# Power.net
KiCad netlist of a schematic drawn in Altium Designer
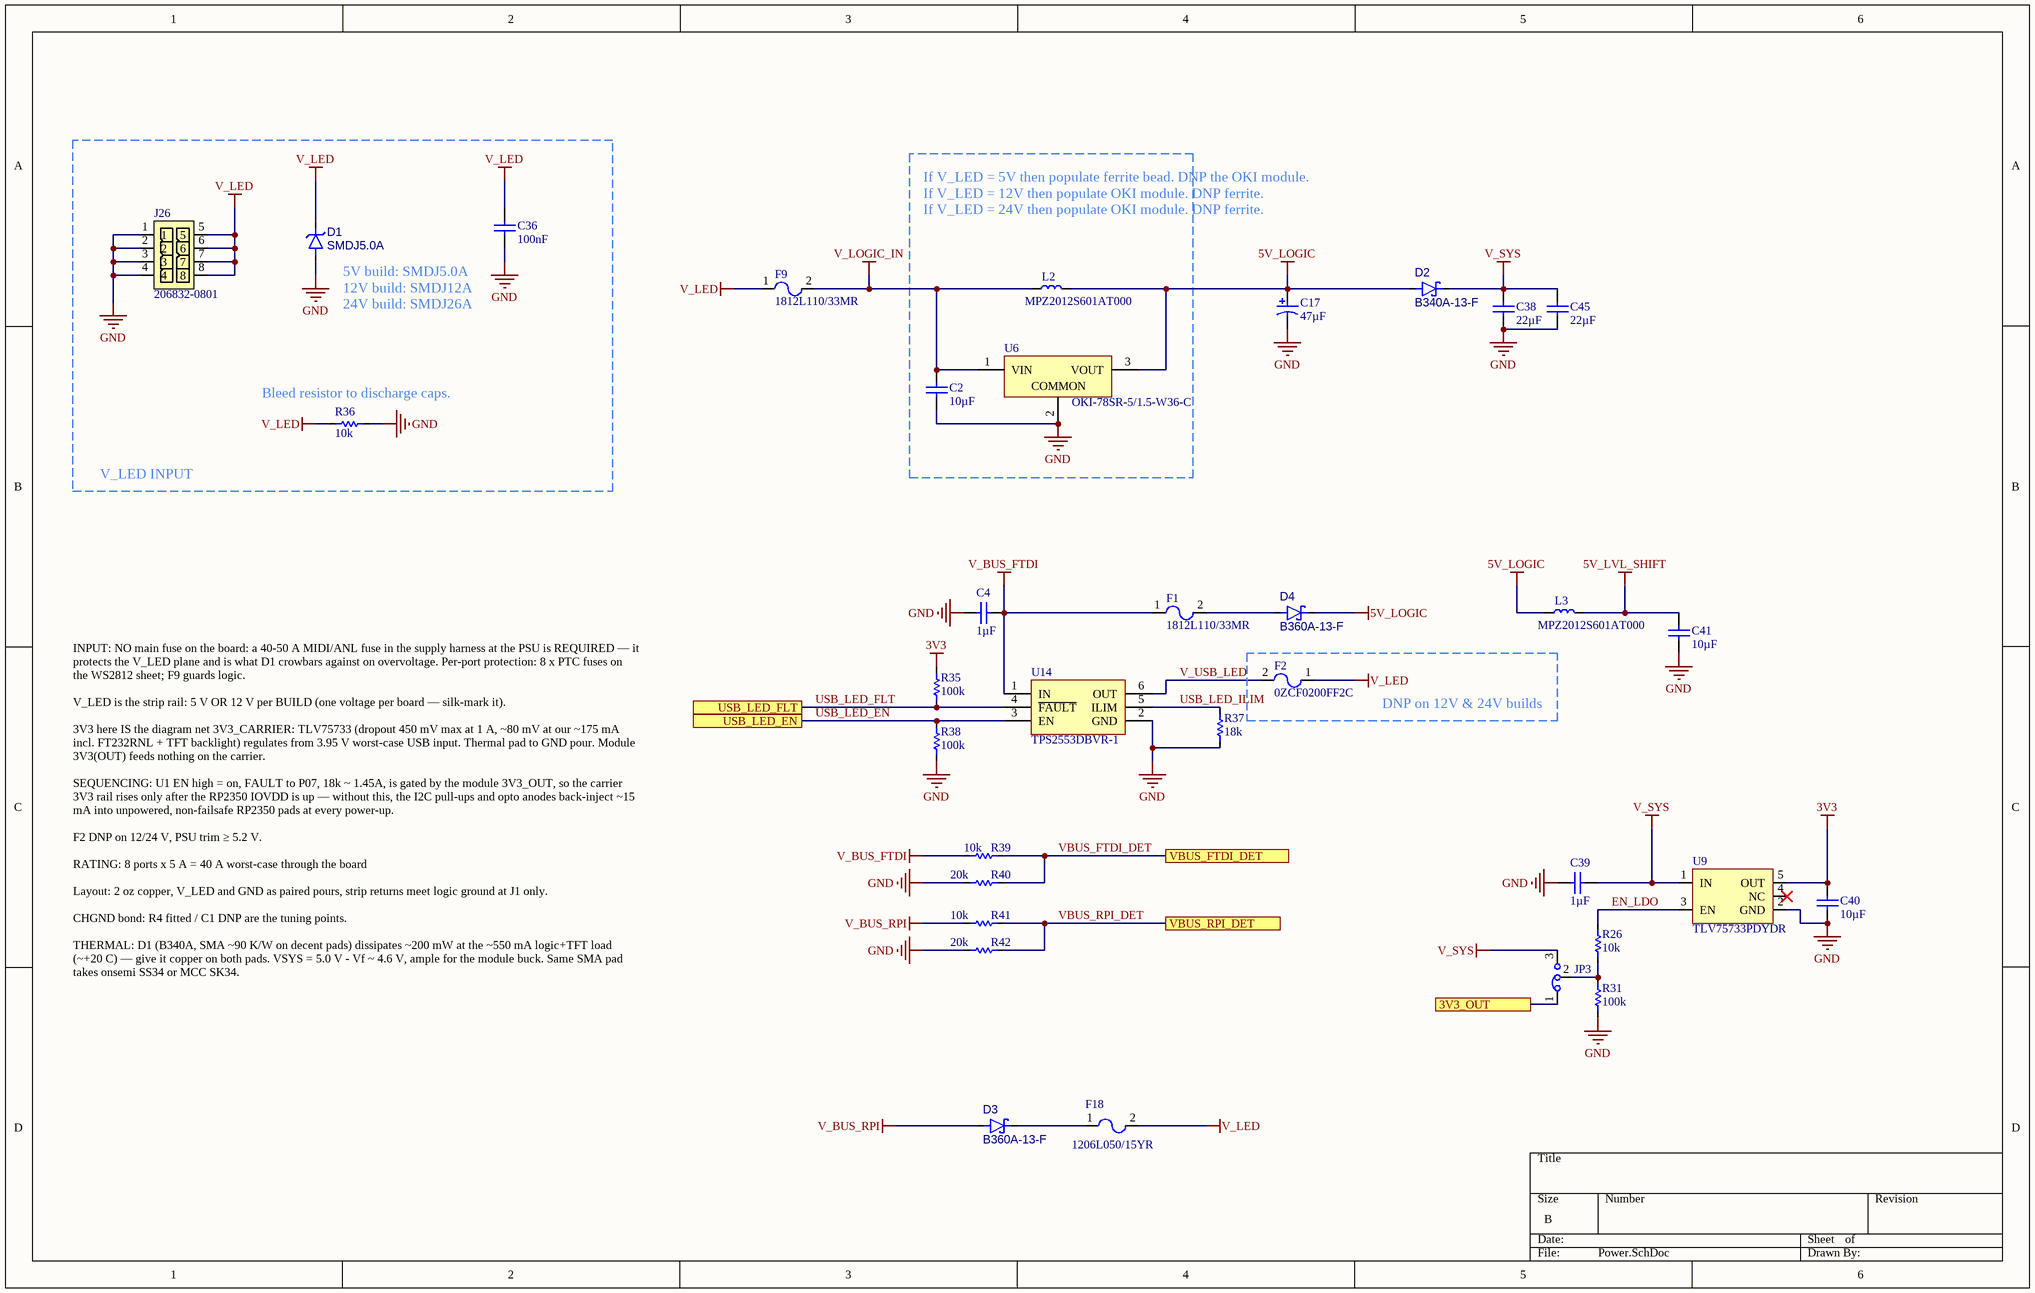
[diagram p0: Power.SchDoc]

(export (version "E")
  (design (tool "Eeschema 10.0.6"))
  (components
    (comp (ref "C2")
      (value "10µF")
      (footprint "CAPC2012X14N_0805_MED")
      (description "Ceramic Capacitor, Multilayer, Ceramic, 10uF, 50V, 10%, X6S, 0805")
      (fields (field (name "TOLERANCE") "10%") (field (name "Comment") "GRM21BR61H106KE43L"))
      (libsource (lib "Equus Computer Systems") (part "CAP-NP-2"))
    )
    (comp (ref "C4")
      (value "1µF")
      (footprint "CAPC1608X10N_0603_MED")
      (fields (field (name "TOLERANCE") "10%") (field (name "Comment") "C1608X7R1C105K080AC"))
      (libsource (lib "Equus Computer Systems") (part "CAP-NP-2"))
    )
    (comp (ref "C17")
      (value "47µF")
      (footprint "FP-SP-Cap-X-MFG")
      (description "Polymer Aluminum Electrolytic Capacitor, 47 µF, -55 to 105 ¡C")
      (fields (field (name "TOLERANCE") "20%") (field (name "Comment") "EEF-CX1C470R"))
      (libsource (lib "Equus Computer Systems") (part "CAP-P-2"))
    )
    (comp (ref "C36")
      (value "100nF")
      (footprint "CAPC1608X10N_0603_MED")
      (fields (field (name "Comment") "CC0603KRX7R0BB104"))
      (libsource (lib "Equus Computer Systems") (part "CAP-NP-2"))
    )
    (comp (ref "C38")
      (value "22µF")
      (footprint "CAPC2012X14N_0805_MED")
      (description "Ceramic Capacitor, Multilayer, Ceramic, 22uF, 16V, 20%, X6S, 0805")
      (fields (field (name "TOLERANCE") "20%") (field (name "Comment") "GRM21BC81C226ME44L"))
      (libsource (lib "Equus Computer Systems") (part "CAP-NP-2"))
    )
    (comp (ref "C39")
      (value "1µF")
      (footprint "CAPC1608X10N_0603_MED")
      (fields (field (name "TOLERANCE") "10%") (field (name "Comment") "C1608X7R1C105K080AC"))
      (libsource (lib "Equus Computer Systems") (part "CAP-NP-2"))
    )
    (comp (ref "C40")
      (value "10µF")
      (footprint "CAPC2012X14N_0805_MED")
      (description "Ceramic Capacitor, Multilayer, Ceramic, 10uF, 16V, 10%, X6S, 0805")
      (fields (field (name "TOLERANCE") "10%") (field (name "Comment") "GRM21BC81C106KA73L"))
      (libsource (lib "Equus Computer Systems") (part "CAP-NP-2"))
    )
    (comp (ref "C41")
      (value "10µF")
      (footprint "CAPC2012X14N_0805_MED")
      (description "Ceramic Capacitor, Multilayer, Ceramic, 10uF, 16V, 10%, X6S, 0805")
      (fields (field (name "TOLERANCE") "10%") (field (name "Comment") "GRM21BC81C106KA73L"))
      (libsource (lib "Equus Computer Systems") (part "CAP-NP-2"))
    )
    (comp (ref "C45")
      (value "22µF")
      (footprint "CAPC2012X14N_0805_MED")
      (description "Ceramic Capacitor, Multilayer, Ceramic, 22uF, 16V, 20%, X6S, 0805")
      (fields (field (name "TOLERANCE") "20%") (field (name "Comment") "GRM21BC81C226ME44L"))
      (libsource (lib "Equus Computer Systems") (part "CAP-NP-2"))
    )
    (comp (ref "D1")
      (value "SMDJ5.0A")
      (footprint "SMDJ_DO-214AB")
      (description "SMDJ Series 6.5 W 7 V Uni-Directional Surface Mount TVS Diode - SMC")
      (libsource (lib "Equus Computer Systems") (part "DIODE-TVS-2"))
    )
    (comp (ref "D2")
      (value "B340A-13-F")
      (footprint "DO-214AC_SMA")
      (description "Rectifier Diode, Schottky, 1 Phase, 1 Element, 3A, 40V V(RRM), Silicon")
      (libsource (lib "Equus Computer Systems") (part "DIODE-SKY-2"))
    )
    (comp (ref "D3")
      (value "B360A-13-F")
      (footprint "FP-SMA-MFG")
      (description "Rectifier Diode, Schottky, 1 Phase, 1 Element, 3A, 60V V(RRM), Silicon, DO-214AC")
      (libsource (lib "Equus Computer Systems") (part "DIODE-SKY-2"))
    )
    (comp (ref "D4")
      (value "B360A-13-F")
      (footprint "FP-SMA-MFG")
      (description "Rectifier Diode, Schottky, 1 Phase, 1 Element, 3A, 60V V(RRM), Silicon, DO-214AC")
      (libsource (lib "Equus Computer Systems") (part "DIODE-SKY-2"))
    )
    (comp (ref "F1")
      (value "1812L110/33MR")
      (footprint "FUSE4532X1.55N_1812MED")
      (description "PTC Resettable Fuse 1.1A(hold) 1.95A(trip) 33VDC 20A 0.8W 0.5s 0.06Ohm SMD Solder Pad 1812 T/R")
      (libsource (lib "Equus Computer Systems") (part "Fuse"))
    )
    (comp (ref "F2")
      (value "0ZCF0200FF2C")
      (footprint "RESC7451X90M_2920")
      (description "SMD Resettable Fuse, PPTC, 2920 [7351 Metric], 0ZCF, 16 VDC, 2 A, 4 A, 4.5 s")
      (libsource (lib "Equus Computer Systems") (part "Fuse"))
    )
    (comp (ref "F9")
      (value "1812L110/33MR")
      (footprint "FUSE4532X1.55N_1812MED")
      (description "PTC Resettable Fuse 1.1A(hold) 1.95A(trip) 33VDC 20A 0.8W 0.5s 0.06Ohm SMD Solder Pad 1812 T/R")
      (libsource (lib "Equus Computer Systems") (part "Fuse"))
    )
    (comp (ref "F18")
      (value "1206L050/15YR")
      (footprint "FP-1206L-MFG")
      (description "PTC Resettable Fuse 0.5A(hold) 1A(trip) 15VDC 100A 0.6W 0.1s 0.15Ohm SMD Solder Pad 1206 T/R")
      (libsource (lib "Equus Computer Systems") (part "Fuse"))
    )
    (comp (ref "J26")
      (value "206832-0801")
      (footprint "206832-0801-Footprint-1")
      (description "Micro-Fit+, Vertical Header, 8 pin")
      (libsource (lib "Equus Computer Systems") (part "206832-0801-Symbol-1"))
    )
    (comp (ref "JP3")
      (value "Jumper 3 x 1 Bridge 1-2 Solder Bridge")
      (footprint "Jumper 3 Solder Bridge 1-2 0603")
      (description "0603 Solder Bridge Jumper Surface Mount")
      (fields (field (name "TOLERANCE") "1%"))
      (libsource (lib "Equus Computer Systems") (part "Jumper 3 Bridge 12"))
    )
    (comp (ref "L2")
      (value "MPZ2012S601AT000")
      (footprint "FP-MPZ2012-MFG")
      (description "Ferrite Beads Multi-Layer Power 600Ohm 25% 100MHz 2A 0.1Ohm DCR 0805 T/R")
      (fields (field (name "TOLERANCE") "25%"))
      (libsource (lib "Equus Computer Systems") (part "IND-2"))
    )
    (comp (ref "L3")
      (value "MPZ2012S601AT000")
      (footprint "FP-MPZ2012-MFG")
      (description "Ferrite Beads Multi-Layer Power 600Ohm 25% 100MHz 2A 0.1Ohm DCR 0805 T/R")
      (fields (field (name "TOLERANCE") "25%"))
      (libsource (lib "Equus Computer Systems") (part "IND-2"))
    )
    (comp (ref "R26")
      (value "10k")
      (footprint "RESC1608X06N_0603_MED")
      (fields
        (field (name "POWER") "100mW")
        (field (name "TOLERANCE") "1%")
        (field (name "Comment") "RC0603FR-1010KL")
      )
      (libsource (lib "Equus Computer Systems") (part "RES-2"))
    )
    (comp (ref "R31")
      (value "100k")
      (footprint "RESC1608X06N_0603_MED")
      (fields
        (field (name "POWER") "100mW")
        (field (name "TOLERANCE") "0.5%")
        (field (name "Comment") "RC0603DR-07100KL")
      )
      (libsource (lib "Equus Computer Systems") (part "RES-2"))
    )
    (comp (ref "R35")
      (value "100k")
      (footprint "RESC1608X06N_0603_MED")
      (fields
        (field (name "POWER") "100mW")
        (field (name "TOLERANCE") "0.5%")
        (field (name "Comment") "RC0603DR-07100KL")
      )
      (libsource (lib "Equus Computer Systems") (part "RES-2"))
    )
    (comp (ref "R36")
      (value "10k")
      (footprint "RESC3116X06N_1206MED")
      (fields
        (field (name "POWER") "250mW")
        (field (name "TOLERANCE") "1%")
        (field (name "Comment") "RC1206FR-0710KL")
      )
      (libsource (lib "Equus Computer Systems") (part "RES-2"))
    )
    (comp (ref "R37")
      (value "18k")
      (footprint "RESC1608X06N_0603_MED")
      (description "100mW Thick Film Resistors 75V ±100ppm/℃ ±1% 18kΩ 0603 Chip Resistor - Surface Mount ROHS")
      (fields (field (name "TOLERANCE") "1%") (field (name "POWER") "100mW"))
      (libsource (lib "Equus Computer Systems") (part "RES-2"))
    )
    (comp (ref "R38")
      (value "100k")
      (footprint "RESC1608X06N_0603_MED")
      (fields
        (field (name "POWER") "100mW")
        (field (name "TOLERANCE") "0.5%")
        (field (name "Comment") "RC0603DR-07100KL")
      )
      (libsource (lib "Equus Computer Systems") (part "RES-2"))
    )
    (comp (ref "R39")
      (value "10k")
      (footprint "RESC1608X06N_0603_MED")
      (fields
        (field (name "POWER") "100mW")
        (field (name "TOLERANCE") "1%")
        (field (name "Comment") "RC0603FR-1010KL")
      )
      (libsource (lib "Equus Computer Systems") (part "RES-2"))
    )
    (comp (ref "R40")
      (value "20k")
      (footprint "RESC1608X06N_0603_MED")
      (description "100mW Thick Film Resistors 75V ±100ppm/℃ ±1% 20kΩ 0603 Chip Resistor - Surface Mount ROHS")
      (fields (field (name "TOLERANCE") "1%") (field (name "POWER") "100mW"))
      (libsource (lib "Equus Computer Systems") (part "RES-2"))
    )
    (comp (ref "R41")
      (value "10k")
      (footprint "RESC1608X06N_0603_MED")
      (fields
        (field (name "POWER") "100mW")
        (field (name "TOLERANCE") "1%")
        (field (name "Comment") "RC0603FR-1010KL")
      )
      (libsource (lib "Equus Computer Systems") (part "RES-2"))
    )
    (comp (ref "R42")
      (value "20k")
      (footprint "RESC1608X06N_0603_MED")
      (description "100mW Thick Film Resistors 75V ±100ppm/℃ ±1% 20kΩ 0603 Chip Resistor - Surface Mount ROHS")
      (fields (field (name "TOLERANCE") "1%") (field (name "POWER") "100mW"))
      (libsource (lib "Equus Computer Systems") (part "RES-2"))
    )
    (comp (ref "U6")
      (value "OKI-78SR-5/1.5-W36-C")
      (footprint "MURA-OKI-78SR-3")
      (description "8 W Single Output 5 V Non Isolated Through Hole DC/DC Converter")
      (libsource (lib "Equus Computer Systems") (part "MURA-OKI-78SR-3"))
    )
    (comp (ref "U9")
      (value "TLV75733PDYDR")
      (footprint "SOT95P280X145-5N")
      (description "1-A, low-IQ high-accuracy low-dropout (LDO) voltage regulator with enable 5-SOT-23 -40 to 125")
      (libsource (lib "Equus Computer Systems") (part "TLV75733PDYDR"))
    )
    (comp (ref "U14")
      (value "TPS2553DBVR-1")
      (footprint "DBV0006A_N")
      (description "IC PWR SWITCH N-CHAN 1: 1 SOT23-6 Power Switch/Driver 1: 1 N-Channel 1.5A SOT-23-6")
      (libsource (lib "Equus Computer Systems") (part "TI-TPS2553-1DBV6"))
    )
  )
  (nets
    (net (code "1") (name "/3V3_OUT") (class "Default")
      (node (ref "JP3") (pin "1") (pinfunction "1_1") (pintype "passive"))
    )
    (net (code "2") (name "/EN_LDO") (class "Default")
      (node (ref "R26") (pin "2") (pinfunction "2_2") (pintype "passive"))
      (node (ref "U9") (pin "3") (pinfunction "EN_3") (pintype "passive"))
    )
    (net (code "3") (name "/USB_LED_EN") (class "Default")
      (node (ref "R38") (pin "1") (pinfunction "1_1") (pintype "passive"))
      (node (ref "U14") (pin "3") (pinfunction "EN_3") (pintype "passive"))
    )
    (net (code "4") (name "/USB_LED_FLT") (class "Default")
      (node (ref "R35") (pin "1") (pinfunction "1_1") (pintype "passive"))
      (node (ref "U14") (pin "4") (pinfunction "~{FAULT}_4") (pintype "tri_state"))
    )
    (net (code "5") (name "/USB_LED_ILIM") (class "Default")
      (node (ref "R37") (pin "2") (pinfunction "2_2") (pintype "passive"))
      (node (ref "U14") (pin "5") (pinfunction "ILIM_5") (pintype "passive"))
    )
    (net (code "6") (name "/VBUS_FTDI_DET") (class "Default")
      (node (ref "R39") (pin "1") (pinfunction "1_1") (pintype "passive"))
      (node (ref "R40") (pin "2") (pinfunction "2_2") (pintype "passive"))
    )
    (net (code "7") (name "/VBUS_RPI_DET") (class "Default")
      (node (ref "R41") (pin "1") (pinfunction "1_1") (pintype "passive"))
      (node (ref "R42") (pin "2") (pinfunction "2_2") (pintype "passive"))
    )
    (net (code "8") (name "/V_USB_LED") (class "Default")
      (node (ref "F2") (pin "2") (pinfunction "2_2") (pintype "passive"))
      (node (ref "U14") (pin "6") (pinfunction "OUT_6") (pintype "power_in"))
    )
    (net (code "9") (name "3V3") (class "Default")
      (node (ref "C40") (pin "2") (pinfunction "2_2") (pintype "passive"))
      (node (ref "R35") (pin "2") (pinfunction "2_2") (pintype "passive"))
      (node (ref "U9") (pin "5") (pinfunction "OUT_5") (pintype "passive"))
    )
    (net (code "10") (name "5V_LOGIC") (class "Default")
      (node (ref "C17") (pin "1") (pinfunction "1_1") (pintype "passive"))
      (node (ref "D2") (pin "2") (pinfunction "A_2") (pintype "passive"))
      (node (ref "D4") (pin "1") (pinfunction "K_1") (pintype "passive"))
      (node (ref "L2") (pin "2") (pinfunction "2_2") (pintype "passive"))
      (node (ref "L3") (pin "1") (pinfunction "1_1") (pintype "passive"))
      (node (ref "U6") (pin "3") (pinfunction "VOUT_3") (pintype "power_in"))
    )
    (net (code "11") (name "5V_LVL_SHIFT") (class "Default")
      (node (ref "C41") (pin "2") (pinfunction "2_2") (pintype "passive"))
      (node (ref "L3") (pin "2") (pinfunction "2_2") (pintype "passive"))
    )
    (net (code "12") (name "GND") (class "Default")
      (node (ref "C17") (pin "2") (pinfunction "2_2") (pintype "passive"))
      (node (ref "C2") (pin "1") (pinfunction "1_1") (pintype "passive"))
      (node (ref "C36") (pin "2") (pinfunction "2_2") (pintype "passive"))
      (node (ref "C38") (pin "1") (pinfunction "1_1") (pintype "passive"))
      (node (ref "C39") (pin "1") (pinfunction "1_1") (pintype "passive"))
      (node (ref "C4") (pin "1") (pinfunction "1_1") (pintype "passive"))
      (node (ref "C40") (pin "1") (pinfunction "1_1") (pintype "passive"))
      (node (ref "C41") (pin "1") (pinfunction "1_1") (pintype "passive"))
      (node (ref "C45") (pin "1") (pinfunction "1_1") (pintype "passive"))
      (node (ref "D1") (pin "2") (pinfunction "A_2") (pintype "passive"))
      (node (ref "J26") (pin "1") (pinfunction "1_1") (pintype "passive"))
      (node (ref "J26") (pin "2") (pinfunction "2_2") (pintype "passive"))
      (node (ref "J26") (pin "3") (pinfunction "3_3") (pintype "passive"))
      (node (ref "J26") (pin "4") (pinfunction "4_4") (pintype "passive"))
      (node (ref "R31") (pin "1") (pinfunction "1_1") (pintype "passive"))
      (node (ref "R36") (pin "2") (pinfunction "2_2") (pintype "passive"))
      (node (ref "R37") (pin "1") (pinfunction "1_1") (pintype "passive"))
      (node (ref "R38") (pin "2") (pinfunction "2_2") (pintype "passive"))
      (node (ref "R40") (pin "1") (pinfunction "1_1") (pintype "passive"))
      (node (ref "R42") (pin "1") (pinfunction "1_1") (pintype "passive"))
      (node (ref "U14") (pin "2") (pinfunction "GND_2") (pintype "power_in"))
      (node (ref "U6") (pin "2") (pinfunction "COMMON_2") (pintype "power_in"))
      (node (ref "U9") (pin "2") (pinfunction "GND_2") (pintype "passive"))
    )
    (net (code "13") (name "Net-(D3-K)") (class "Default")
      (node (ref "D3") (pin "1") (pinfunction "K_1") (pintype "passive"))
      (node (ref "F18") (pin "1") (pinfunction "1_1") (pintype "passive"))
    )
    (net (code "14") (name "Net-(D4-A)") (class "Default")
      (node (ref "D4") (pin "2") (pinfunction "A_2") (pintype "passive"))
      (node (ref "F1") (pin "2") (pinfunction "2_2") (pintype "passive"))
    )
    (net (code "15") (name "Net-(JP3-Pad2)") (class "Default")
      (node (ref "JP3") (pin "2") (pinfunction "2_2") (pintype "passive"))
      (node (ref "R26") (pin "1") (pinfunction "1_1") (pintype "passive"))
      (node (ref "R31") (pin "2") (pinfunction "2_2") (pintype "passive"))
    )
    (net (code "16") (name "V_BUS_FTDI") (class "Default")
      (node (ref "C4") (pin "2") (pinfunction "2_2") (pintype "passive"))
      (node (ref "F1") (pin "1") (pinfunction "1_1") (pintype "passive"))
      (node (ref "R39") (pin "2") (pinfunction "2_2") (pintype "passive"))
      (node (ref "U14") (pin "1") (pinfunction "IN_1") (pintype "power_in"))
    )
    (net (code "17") (name "V_BUS_RPI") (class "Default")
      (node (ref "D3") (pin "2") (pinfunction "A_2") (pintype "passive"))
      (node (ref "R41") (pin "2") (pinfunction "2_2") (pintype "passive"))
    )
    (net (code "18") (name "V_LED") (class "Default")
      (node (ref "C36") (pin "1") (pinfunction "1_1") (pintype "passive"))
      (node (ref "D1") (pin "1") (pinfunction "K_1") (pintype "passive"))
      (node (ref "F18") (pin "2") (pinfunction "2_2") (pintype "passive"))
      (node (ref "F2") (pin "1") (pinfunction "1_1") (pintype "passive"))
      (node (ref "F9") (pin "1") (pinfunction "1_1") (pintype "passive"))
      (node (ref "J26") (pin "5") (pinfunction "5_5") (pintype "passive"))
      (node (ref "J26") (pin "6") (pinfunction "6_6") (pintype "passive"))
      (node (ref "J26") (pin "7") (pinfunction "7_7") (pintype "passive"))
      (node (ref "J26") (pin "8") (pinfunction "8_8") (pintype "passive"))
      (node (ref "R36") (pin "1") (pinfunction "1_1") (pintype "passive"))
    )
    (net (code "19") (name "V_LOGIC_IN") (class "Default")
      (node (ref "C2") (pin "2") (pinfunction "2_2") (pintype "passive"))
      (node (ref "F9") (pin "2") (pinfunction "2_2") (pintype "passive"))
      (node (ref "L2") (pin "1") (pinfunction "1_1") (pintype "passive"))
      (node (ref "U6") (pin "1") (pinfunction "VIN_1") (pintype "power_in"))
    )
    (net (code "20") (name "V_SYS") (class "Default")
      (node (ref "C38") (pin "2") (pinfunction "2_2") (pintype "passive"))
      (node (ref "C39") (pin "2") (pinfunction "2_2") (pintype "passive"))
      (node (ref "C45") (pin "2") (pinfunction "2_2") (pintype "passive"))
      (node (ref "D2") (pin "1") (pinfunction "K_1") (pintype "passive"))
      (node (ref "JP3") (pin "3") (pinfunction "3_3") (pintype "passive"))
      (node (ref "U9") (pin "1") (pinfunction "IN_1") (pintype "passive"))
    )
    (net (code "21") (name "unconnected-(U9-NC-Pad4)") (class "Default")
      (node (ref "U9") (pin "4") (pinfunction "NC_4") (pintype "passive+no_connect"))
    )
  )
)
